# 3_3M_Transistor_Logic.net
KiCad netlist of a schematic drawn in Altium Designer
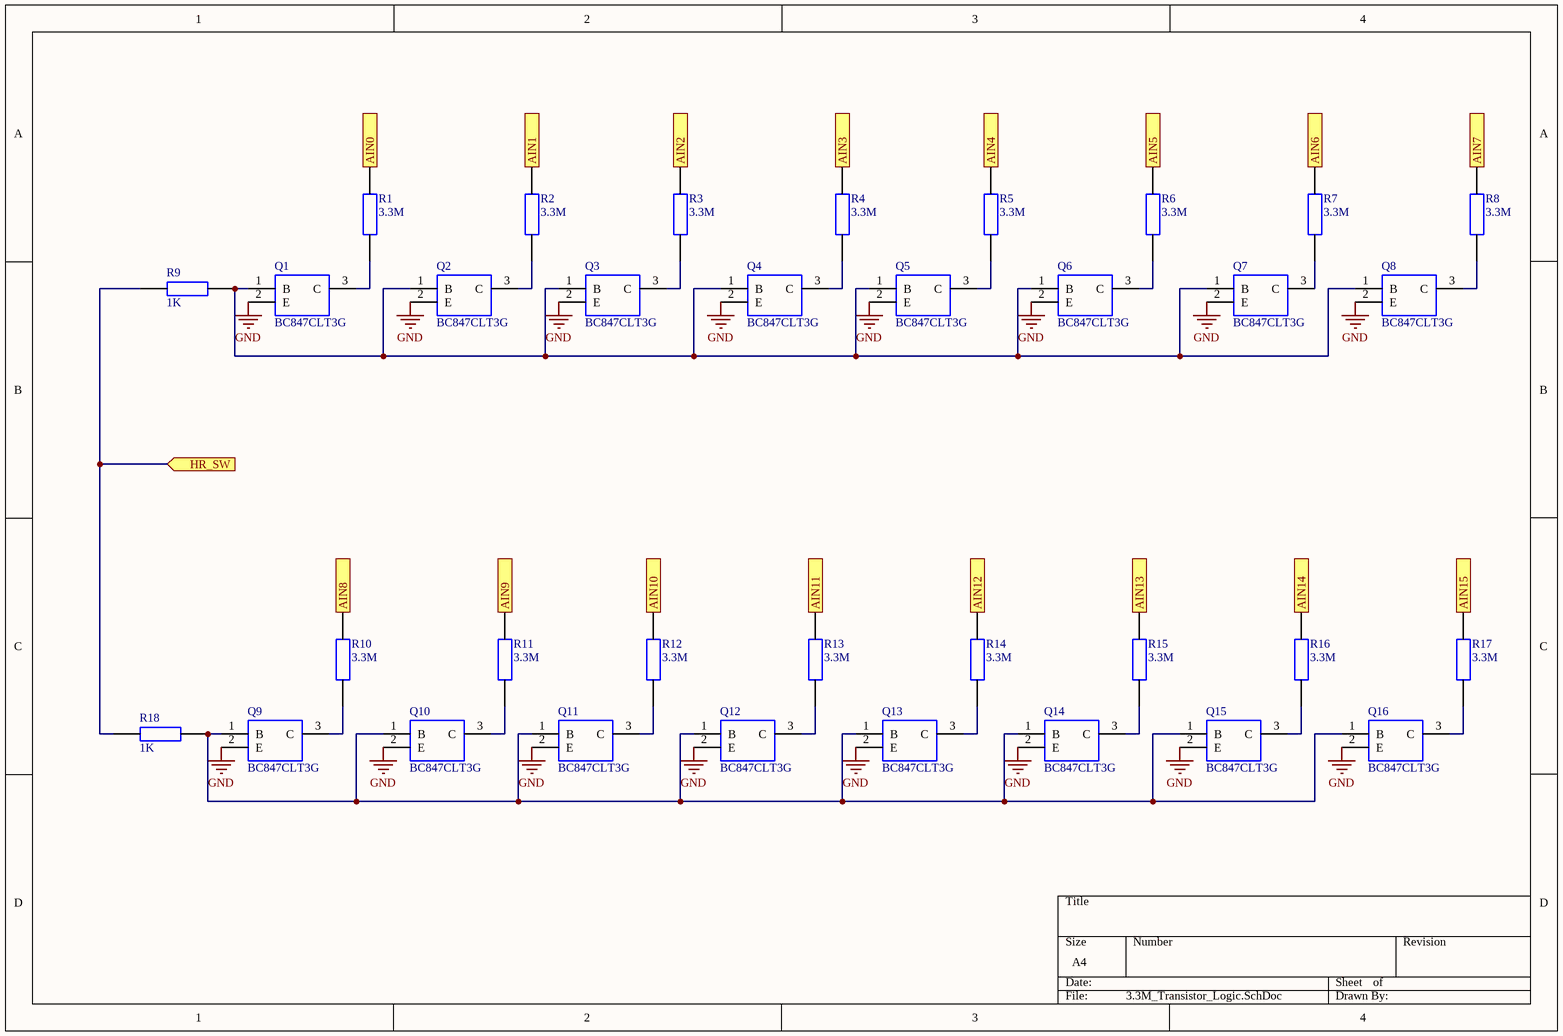
[diagram p0: 3.3M_Transistor_Logic.SchDoc]

(export (version "E")
  (design (tool "Eeschema 10.0.6"))
  (components
    (comp (ref "Q1")
      (value "BC847CLT3G")
      (footprint "SOT96P237X111-3N")
      (fields (field (name "MOUSER PART NUMBER") "863-BC847CLT3G"))
      (libsource (lib "BC847CLT3G") (part "BC847CLT3G"))
    )
    (comp (ref "Q2")
      (value "BC847CLT3G")
      (footprint "SOT96P237X111-3N")
      (fields (field (name "MOUSER PART NUMBER") "863-BC847CLT3G"))
      (libsource (lib "BC847CLT3G") (part "BC847CLT3G"))
    )
    (comp (ref "Q3")
      (value "BC847CLT3G")
      (footprint "SOT96P237X111-3N")
      (fields (field (name "MOUSER PART NUMBER") "863-BC847CLT3G"))
      (libsource (lib "BC847CLT3G") (part "BC847CLT3G"))
    )
    (comp (ref "Q4")
      (value "BC847CLT3G")
      (footprint "SOT96P237X111-3N")
      (fields (field (name "MOUSER PART NUMBER") "863-BC847CLT3G"))
      (libsource (lib "BC847CLT3G") (part "BC847CLT3G"))
    )
    (comp (ref "Q5")
      (value "BC847CLT3G")
      (footprint "SOT96P237X111-3N")
      (fields (field (name "MOUSER PART NUMBER") "863-BC847CLT3G"))
      (libsource (lib "BC847CLT3G") (part "BC847CLT3G"))
    )
    (comp (ref "Q6")
      (value "BC847CLT3G")
      (footprint "SOT96P237X111-3N")
      (fields (field (name "MOUSER PART NUMBER") "863-BC847CLT3G"))
      (libsource (lib "BC847CLT3G") (part "BC847CLT3G"))
    )
    (comp (ref "Q7")
      (value "BC847CLT3G")
      (footprint "SOT96P237X111-3N")
      (fields (field (name "MOUSER PART NUMBER") "863-BC847CLT3G"))
      (libsource (lib "BC847CLT3G") (part "BC847CLT3G"))
    )
    (comp (ref "Q8")
      (value "BC847CLT3G")
      (footprint "SOT96P237X111-3N")
      (fields (field (name "MOUSER PART NUMBER") "863-BC847CLT3G"))
      (libsource (lib "BC847CLT3G") (part "BC847CLT3G"))
    )
    (comp (ref "Q9")
      (value "BC847CLT3G")
      (footprint "SOT96P237X111-3N")
      (fields (field (name "MOUSER PART NUMBER") "863-BC847CLT3G"))
      (libsource (lib "BC847CLT3G") (part "BC847CLT3G"))
    )
    (comp (ref "Q10")
      (value "BC847CLT3G")
      (footprint "SOT96P237X111-3N")
      (fields (field (name "MOUSER PART NUMBER") "863-BC847CLT3G"))
      (libsource (lib "BC847CLT3G") (part "BC847CLT3G"))
    )
    (comp (ref "Q11")
      (value "BC847CLT3G")
      (footprint "SOT96P237X111-3N")
      (fields (field (name "MOUSER PART NUMBER") "863-BC847CLT3G"))
      (libsource (lib "BC847CLT3G") (part "BC847CLT3G"))
    )
    (comp (ref "Q12")
      (value "BC847CLT3G")
      (footprint "SOT96P237X111-3N")
      (fields (field (name "MOUSER PART NUMBER") "863-BC847CLT3G"))
      (libsource (lib "BC847CLT3G") (part "BC847CLT3G"))
    )
    (comp (ref "Q13")
      (value "BC847CLT3G")
      (footprint "SOT96P237X111-3N")
      (fields (field (name "MOUSER PART NUMBER") "863-BC847CLT3G"))
      (libsource (lib "BC847CLT3G") (part "BC847CLT3G"))
    )
    (comp (ref "Q14")
      (value "BC847CLT3G")
      (footprint "SOT96P237X111-3N")
      (fields (field (name "MOUSER PART NUMBER") "863-BC847CLT3G"))
      (libsource (lib "BC847CLT3G") (part "BC847CLT3G"))
    )
    (comp (ref "Q15")
      (value "BC847CLT3G")
      (footprint "SOT96P237X111-3N")
      (fields (field (name "MOUSER PART NUMBER") "863-BC847CLT3G"))
      (libsource (lib "BC847CLT3G") (part "BC847CLT3G"))
    )
    (comp (ref "Q16")
      (value "BC847CLT3G")
      (footprint "SOT96P237X111-3N")
      (fields (field (name "MOUSER PART NUMBER") "863-BC847CLT3G"))
      (libsource (lib "BC847CLT3G") (part "BC847CLT3G"))
    )
    (comp (ref "R1")
      (value "3.3M")
      (footprint "RESC1608X55N")
      (description "YAGEO (PHYCOMP) - RC0603FR-07330RL - RES, THICK FILM, 330R, 1%, 0.1W, 0603")
      (fields
        (field (name "MANUFACTURER_PART_NUMBER") "RC0603FR-07330RL")
        (field (name "MOUSER PART NUMBER") "603-RC0603FR-07330RL")
      )
      (libsource (lib "330E_0603") (part "RC0603FR-07330RL"))
    )
    (comp (ref "R2")
      (value "3.3M")
      (footprint "RESC1608X55N")
      (description "YAGEO (PHYCOMP) - RC0603FR-07330RL - RES, THICK FILM, 330R, 1%, 0.1W, 0603")
      (fields
        (field (name "MANUFACTURER_PART_NUMBER") "RC0603FR-07330RL")
        (field (name "MOUSER PART NUMBER") "603-RC0603FR-07330RL")
      )
      (libsource (lib "330E_0603") (part "RC0603FR-07330RL"))
    )
    (comp (ref "R3")
      (value "3.3M")
      (footprint "RESC1608X55N")
      (description "YAGEO (PHYCOMP) - RC0603FR-07330RL - RES, THICK FILM, 330R, 1%, 0.1W, 0603")
      (fields
        (field (name "MANUFACTURER_PART_NUMBER") "RC0603FR-07330RL")
        (field (name "MOUSER PART NUMBER") "603-RC0603FR-07330RL")
      )
      (libsource (lib "330E_0603") (part "RC0603FR-07330RL"))
    )
    (comp (ref "R4")
      (value "3.3M")
      (footprint "RESC1608X55N")
      (description "YAGEO (PHYCOMP) - RC0603FR-07330RL - RES, THICK FILM, 330R, 1%, 0.1W, 0603")
      (fields
        (field (name "MANUFACTURER_PART_NUMBER") "RC0603FR-07330RL")
        (field (name "MOUSER PART NUMBER") "603-RC0603FR-07330RL")
      )
      (libsource (lib "330E_0603") (part "RC0603FR-07330RL"))
    )
    (comp (ref "R5")
      (value "3.3M")
      (footprint "RESC1608X55N")
      (description "YAGEO (PHYCOMP) - RC0603FR-07330RL - RES, THICK FILM, 330R, 1%, 0.1W, 0603")
      (fields
        (field (name "MANUFACTURER_PART_NUMBER") "RC0603FR-07330RL")
        (field (name "MOUSER PART NUMBER") "603-RC0603FR-07330RL")
      )
      (libsource (lib "330E_0603") (part "RC0603FR-07330RL"))
    )
    (comp (ref "R6")
      (value "3.3M")
      (footprint "RESC1608X55N")
      (description "YAGEO (PHYCOMP) - RC0603FR-07330RL - RES, THICK FILM, 330R, 1%, 0.1W, 0603")
      (fields
        (field (name "MANUFACTURER_PART_NUMBER") "RC0603FR-07330RL")
        (field (name "MOUSER PART NUMBER") "603-RC0603FR-07330RL")
      )
      (libsource (lib "330E_0603") (part "RC0603FR-07330RL"))
    )
    (comp (ref "R7")
      (value "3.3M")
      (footprint "RESC1608X55N")
      (description "YAGEO (PHYCOMP) - RC0603FR-07330RL - RES, THICK FILM, 330R, 1%, 0.1W, 0603")
      (fields
        (field (name "MANUFACTURER_PART_NUMBER") "RC0603FR-07330RL")
        (field (name "MOUSER PART NUMBER") "603-RC0603FR-07330RL")
      )
      (libsource (lib "330E_0603") (part "RC0603FR-07330RL"))
    )
    (comp (ref "R8")
      (value "3.3M")
      (footprint "RESC1608X55N")
      (description "YAGEO (PHYCOMP) - RC0603FR-07330RL - RES, THICK FILM, 330R, 1%, 0.1W, 0603")
      (fields
        (field (name "MANUFACTURER_PART_NUMBER") "RC0603FR-07330RL")
        (field (name "MOUSER PART NUMBER") "603-RC0603FR-07330RL")
      )
      (libsource (lib "330E_0603") (part "RC0603FR-07330RL"))
    )
    (comp (ref "R9")
      (value "1K")
      (footprint "RESC1608X55N")
      (description "YAGEO (PHYCOMP) - RC0603JR-071KL - RES, THICK FILM, 1K, 5%, 0.1W, 0603")
      (fields
        (field (name "MANUFACTURER_PART_NUMBER") "RC0603JR-071KL")
        (field (name "MOUSER PART NUMBER") "603-RC0603JR-071KL")
      )
      (libsource (lib "1K_0603") (part "RC0603JR-071KL"))
    )
    (comp (ref "R10")
      (value "3.3M")
      (footprint "RESC1608X55N")
      (description "YAGEO (PHYCOMP) - RC0603FR-07330RL - RES, THICK FILM, 330R, 1%, 0.1W, 0603")
      (fields
        (field (name "MANUFACTURER_PART_NUMBER") "RC0603FR-07330RL")
        (field (name "MOUSER PART NUMBER") "603-RC0603FR-07330RL")
      )
      (libsource (lib "330E_0603") (part "RC0603FR-07330RL"))
    )
    (comp (ref "R11")
      (value "3.3M")
      (footprint "RESC1608X55N")
      (description "YAGEO (PHYCOMP) - RC0603FR-07330RL - RES, THICK FILM, 330R, 1%, 0.1W, 0603")
      (fields
        (field (name "MANUFACTURER_PART_NUMBER") "RC0603FR-07330RL")
        (field (name "MOUSER PART NUMBER") "603-RC0603FR-07330RL")
      )
      (libsource (lib "330E_0603") (part "RC0603FR-07330RL"))
    )
    (comp (ref "R12")
      (value "3.3M")
      (footprint "RESC1608X55N")
      (description "YAGEO (PHYCOMP) - RC0603FR-07330RL - RES, THICK FILM, 330R, 1%, 0.1W, 0603")
      (fields
        (field (name "MANUFACTURER_PART_NUMBER") "RC0603FR-07330RL")
        (field (name "MOUSER PART NUMBER") "603-RC0603FR-07330RL")
      )
      (libsource (lib "330E_0603") (part "RC0603FR-07330RL"))
    )
    (comp (ref "R13")
      (value "3.3M")
      (footprint "RESC1608X55N")
      (description "YAGEO (PHYCOMP) - RC0603FR-07330RL - RES, THICK FILM, 330R, 1%, 0.1W, 0603")
      (fields
        (field (name "MANUFACTURER_PART_NUMBER") "RC0603FR-07330RL")
        (field (name "MOUSER PART NUMBER") "603-RC0603FR-07330RL")
      )
      (libsource (lib "330E_0603") (part "RC0603FR-07330RL"))
    )
    (comp (ref "R14")
      (value "3.3M")
      (footprint "RESC1608X55N")
      (description "YAGEO (PHYCOMP) - RC0603FR-07330RL - RES, THICK FILM, 330R, 1%, 0.1W, 0603")
      (fields
        (field (name "MANUFACTURER_PART_NUMBER") "RC0603FR-07330RL")
        (field (name "MOUSER PART NUMBER") "603-RC0603FR-07330RL")
      )
      (libsource (lib "330E_0603") (part "RC0603FR-07330RL"))
    )
    (comp (ref "R15")
      (value "3.3M")
      (footprint "RESC1608X55N")
      (description "YAGEO (PHYCOMP) - RC0603FR-07330RL - RES, THICK FILM, 330R, 1%, 0.1W, 0603")
      (fields
        (field (name "MANUFACTURER_PART_NUMBER") "RC0603FR-07330RL")
        (field (name "MOUSER PART NUMBER") "603-RC0603FR-07330RL")
      )
      (libsource (lib "330E_0603") (part "RC0603FR-07330RL"))
    )
    (comp (ref "R16")
      (value "3.3M")
      (footprint "RESC1608X55N")
      (description "YAGEO (PHYCOMP) - RC0603FR-07330RL - RES, THICK FILM, 330R, 1%, 0.1W, 0603")
      (fields
        (field (name "MANUFACTURER_PART_NUMBER") "RC0603FR-07330RL")
        (field (name "MOUSER PART NUMBER") "603-RC0603FR-07330RL")
      )
      (libsource (lib "330E_0603") (part "RC0603FR-07330RL"))
    )
    (comp (ref "R17")
      (value "3.3M")
      (footprint "RESC1608X55N")
      (description "YAGEO (PHYCOMP) - RC0603FR-07330RL - RES, THICK FILM, 330R, 1%, 0.1W, 0603")
      (fields
        (field (name "MANUFACTURER_PART_NUMBER") "RC0603FR-07330RL")
        (field (name "MOUSER PART NUMBER") "603-RC0603FR-07330RL")
      )
      (libsource (lib "330E_0603") (part "RC0603FR-07330RL"))
    )
    (comp (ref "R18")
      (value "1K")
      (footprint "RESC1608X55N")
      (description "YAGEO (PHYCOMP) - RC0603JR-071KL - RES, THICK FILM, 1K, 5%, 0.1W, 0603")
      (fields
        (field (name "MANUFACTURER_PART_NUMBER") "RC0603JR-071KL")
        (field (name "MOUSER PART NUMBER") "603-RC0603JR-071KL")
      )
      (libsource (lib "1K_0603") (part "RC0603JR-071KL"))
    )
  )
  (nets
    (net (code "1") (name "/AIN0") (class "Default")
      (node (ref "R1") (pin "2") (pinfunction "2_2") (pintype "passive"))
    )
    (net (code "2") (name "/AIN1") (class "Default")
      (node (ref "R2") (pin "2") (pinfunction "2_2") (pintype "passive"))
    )
    (net (code "3") (name "/AIN2") (class "Default")
      (node (ref "R3") (pin "2") (pinfunction "2_2") (pintype "passive"))
    )
    (net (code "4") (name "/AIN3") (class "Default")
      (node (ref "R4") (pin "2") (pinfunction "2_2") (pintype "passive"))
    )
    (net (code "5") (name "/AIN4") (class "Default")
      (node (ref "R5") (pin "2") (pinfunction "2_2") (pintype "passive"))
    )
    (net (code "6") (name "/AIN5") (class "Default")
      (node (ref "R6") (pin "2") (pinfunction "2_2") (pintype "passive"))
    )
    (net (code "7") (name "/AIN6") (class "Default")
      (node (ref "R7") (pin "2") (pinfunction "2_2") (pintype "passive"))
    )
    (net (code "8") (name "/AIN7") (class "Default")
      (node (ref "R8") (pin "2") (pinfunction "2_2") (pintype "passive"))
    )
    (net (code "9") (name "/AIN8") (class "Default")
      (node (ref "R10") (pin "2") (pinfunction "2_2") (pintype "passive"))
    )
    (net (code "10") (name "/AIN9") (class "Default")
      (node (ref "R11") (pin "2") (pinfunction "2_2") (pintype "passive"))
    )
    (net (code "11") (name "/AIN10") (class "Default")
      (node (ref "R12") (pin "2") (pinfunction "2_2") (pintype "passive"))
    )
    (net (code "12") (name "/AIN11") (class "Default")
      (node (ref "R13") (pin "2") (pinfunction "2_2") (pintype "passive"))
    )
    (net (code "13") (name "/AIN12") (class "Default")
      (node (ref "R14") (pin "2") (pinfunction "2_2") (pintype "passive"))
    )
    (net (code "14") (name "/AIN13") (class "Default")
      (node (ref "R15") (pin "2") (pinfunction "2_2") (pintype "passive"))
    )
    (net (code "15") (name "/AIN14") (class "Default")
      (node (ref "R16") (pin "2") (pinfunction "2_2") (pintype "passive"))
    )
    (net (code "16") (name "/AIN15") (class "Default")
      (node (ref "R17") (pin "2") (pinfunction "2_2") (pintype "passive"))
    )
    (net (code "17") (name "/HR_SW") (class "Default")
      (node (ref "R18") (pin "1") (pinfunction "1_1") (pintype "passive"))
      (node (ref "R9") (pin "1") (pinfunction "1_1") (pintype "passive"))
    )
    (net (code "18") (name "GND") (class "Default")
      (node (ref "Q1") (pin "2") (pinfunction "E_2") (pintype "passive"))
      (node (ref "Q10") (pin "2") (pinfunction "E_2") (pintype "passive"))
      (node (ref "Q11") (pin "2") (pinfunction "E_2") (pintype "passive"))
      (node (ref "Q12") (pin "2") (pinfunction "E_2") (pintype "passive"))
      (node (ref "Q13") (pin "2") (pinfunction "E_2") (pintype "passive"))
      (node (ref "Q14") (pin "2") (pinfunction "E_2") (pintype "passive"))
      (node (ref "Q15") (pin "2") (pinfunction "E_2") (pintype "passive"))
      (node (ref "Q16") (pin "2") (pinfunction "E_2") (pintype "passive"))
      (node (ref "Q2") (pin "2") (pinfunction "E_2") (pintype "passive"))
      (node (ref "Q3") (pin "2") (pinfunction "E_2") (pintype "passive"))
      (node (ref "Q4") (pin "2") (pinfunction "E_2") (pintype "passive"))
      (node (ref "Q5") (pin "2") (pinfunction "E_2") (pintype "passive"))
      (node (ref "Q6") (pin "2") (pinfunction "E_2") (pintype "passive"))
      (node (ref "Q7") (pin "2") (pinfunction "E_2") (pintype "passive"))
      (node (ref "Q8") (pin "2") (pinfunction "E_2") (pintype "passive"))
      (node (ref "Q9") (pin "2") (pinfunction "E_2") (pintype "passive"))
    )
    (net (code "19") (name "Net-(Q1-B)") (class "Default")
      (node (ref "Q1") (pin "1") (pinfunction "B_1") (pintype "passive"))
      (node (ref "Q2") (pin "1") (pinfunction "B_1") (pintype "passive"))
      (node (ref "Q3") (pin "1") (pinfunction "B_1") (pintype "passive"))
      (node (ref "Q4") (pin "1") (pinfunction "B_1") (pintype "passive"))
      (node (ref "Q5") (pin "1") (pinfunction "B_1") (pintype "passive"))
      (node (ref "Q6") (pin "1") (pinfunction "B_1") (pintype "passive"))
      (node (ref "Q7") (pin "1") (pinfunction "B_1") (pintype "passive"))
      (node (ref "Q8") (pin "1") (pinfunction "B_1") (pintype "passive"))
      (node (ref "R9") (pin "2") (pinfunction "2_2") (pintype "passive"))
    )
    (net (code "20") (name "Net-(Q1-C)") (class "Default")
      (node (ref "Q1") (pin "3") (pinfunction "C_3") (pintype "passive"))
      (node (ref "R1") (pin "1") (pinfunction "1_1") (pintype "passive"))
    )
    (net (code "21") (name "Net-(Q2-C)") (class "Default")
      (node (ref "Q2") (pin "3") (pinfunction "C_3") (pintype "passive"))
      (node (ref "R2") (pin "1") (pinfunction "1_1") (pintype "passive"))
    )
    (net (code "22") (name "Net-(Q3-C)") (class "Default")
      (node (ref "Q3") (pin "3") (pinfunction "C_3") (pintype "passive"))
      (node (ref "R3") (pin "1") (pinfunction "1_1") (pintype "passive"))
    )
    (net (code "23") (name "Net-(Q4-C)") (class "Default")
      (node (ref "Q4") (pin "3") (pinfunction "C_3") (pintype "passive"))
      (node (ref "R4") (pin "1") (pinfunction "1_1") (pintype "passive"))
    )
    (net (code "24") (name "Net-(Q5-C)") (class "Default")
      (node (ref "Q5") (pin "3") (pinfunction "C_3") (pintype "passive"))
      (node (ref "R5") (pin "1") (pinfunction "1_1") (pintype "passive"))
    )
    (net (code "25") (name "Net-(Q6-C)") (class "Default")
      (node (ref "Q6") (pin "3") (pinfunction "C_3") (pintype "passive"))
      (node (ref "R6") (pin "1") (pinfunction "1_1") (pintype "passive"))
    )
    (net (code "26") (name "Net-(Q7-C)") (class "Default")
      (node (ref "Q7") (pin "3") (pinfunction "C_3") (pintype "passive"))
      (node (ref "R7") (pin "1") (pinfunction "1_1") (pintype "passive"))
    )
    (net (code "27") (name "Net-(Q8-C)") (class "Default")
      (node (ref "Q8") (pin "3") (pinfunction "C_3") (pintype "passive"))
      (node (ref "R8") (pin "1") (pinfunction "1_1") (pintype "passive"))
    )
    (net (code "28") (name "Net-(Q9-C)") (class "Default")
      (node (ref "Q9") (pin "3") (pinfunction "C_3") (pintype "passive"))
      (node (ref "R10") (pin "1") (pinfunction "1_1") (pintype "passive"))
    )
    (net (code "29") (name "Net-(Q10-B)") (class "Default")
      (node (ref "Q10") (pin "1") (pinfunction "B_1") (pintype "passive"))
      (node (ref "Q11") (pin "1") (pinfunction "B_1") (pintype "passive"))
      (node (ref "Q12") (pin "1") (pinfunction "B_1") (pintype "passive"))
      (node (ref "Q13") (pin "1") (pinfunction "B_1") (pintype "passive"))
      (node (ref "Q14") (pin "1") (pinfunction "B_1") (pintype "passive"))
      (node (ref "Q15") (pin "1") (pinfunction "B_1") (pintype "passive"))
      (node (ref "Q16") (pin "1") (pinfunction "B_1") (pintype "passive"))
      (node (ref "Q9") (pin "1") (pinfunction "B_1") (pintype "passive"))
      (node (ref "R18") (pin "2") (pinfunction "2_2") (pintype "passive"))
    )
    (net (code "30") (name "Net-(Q10-C)") (class "Default")
      (node (ref "Q10") (pin "3") (pinfunction "C_3") (pintype "passive"))
      (node (ref "R11") (pin "1") (pinfunction "1_1") (pintype "passive"))
    )
    (net (code "31") (name "Net-(Q11-C)") (class "Default")
      (node (ref "Q11") (pin "3") (pinfunction "C_3") (pintype "passive"))
      (node (ref "R12") (pin "1") (pinfunction "1_1") (pintype "passive"))
    )
    (net (code "32") (name "Net-(Q12-C)") (class "Default")
      (node (ref "Q12") (pin "3") (pinfunction "C_3") (pintype "passive"))
      (node (ref "R13") (pin "1") (pinfunction "1_1") (pintype "passive"))
    )
    (net (code "33") (name "Net-(Q13-C)") (class "Default")
      (node (ref "Q13") (pin "3") (pinfunction "C_3") (pintype "passive"))
      (node (ref "R14") (pin "1") (pinfunction "1_1") (pintype "passive"))
    )
    (net (code "34") (name "Net-(Q14-C)") (class "Default")
      (node (ref "Q14") (pin "3") (pinfunction "C_3") (pintype "passive"))
      (node (ref "R15") (pin "1") (pinfunction "1_1") (pintype "passive"))
    )
    (net (code "35") (name "Net-(Q15-C)") (class "Default")
      (node (ref "Q15") (pin "3") (pinfunction "C_3") (pintype "passive"))
      (node (ref "R16") (pin "1") (pinfunction "1_1") (pintype "passive"))
    )
    (net (code "36") (name "Net-(Q16-C)") (class "Default")
      (node (ref "Q16") (pin "3") (pinfunction "C_3") (pintype "passive"))
      (node (ref "R17") (pin "1") (pinfunction "1_1") (pintype "passive"))
    )
  )
)
